# infnoise_usbpins.net
KiCad netlist of a schematic drawn in EAGLE
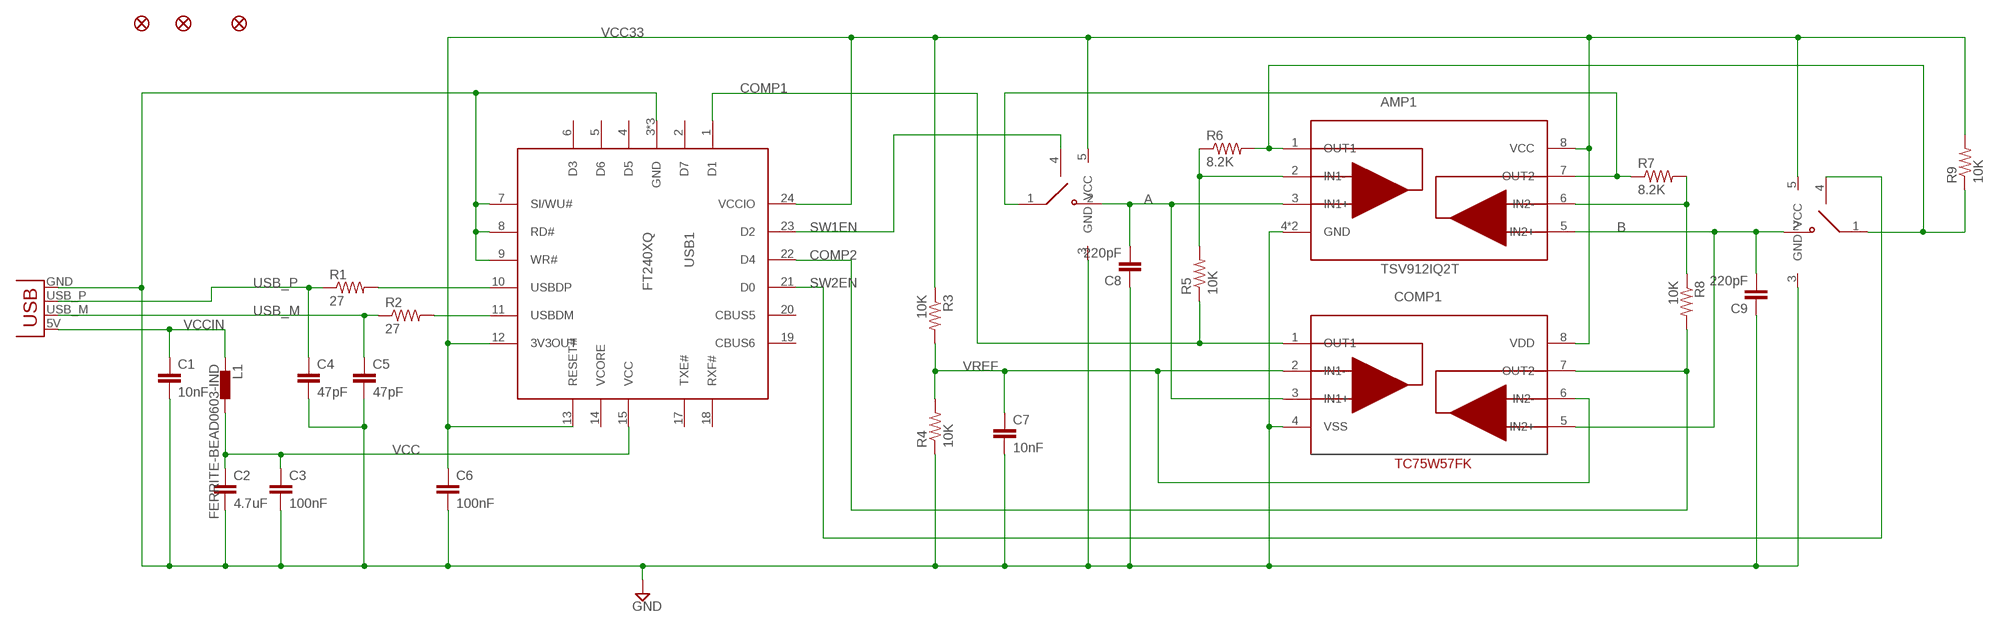
[diagram p0: schematic, sheet 1]

(export (version "E")
  (design (tool "Eeschema 10.0.6"))
  (components
    (comp (ref "AMP1")
      (value "TSV912IQ2T")
      (footprint "eagle-import:DFN8-2X3")
      (libsource (lib "eagle-import") (part "TSV912IQ2T"))
    )
    (comp (ref "C1")
      (value "10nF")
      (footprint "eagle-import:0603-CAP")
      (libsource (lib "eagle-import") (part "CAP0603-CAP"))
    )
    (comp (ref "C2")
      (value "4.7uF")
      (footprint "eagle-import:0603-CAP")
      (libsource (lib "eagle-import") (part "CAP0603-CAP"))
    )
    (comp (ref "C3")
      (value "100nF")
      (footprint "eagle-import:0603-CAP")
      (libsource (lib "eagle-import") (part "CAP0603-CAP"))
    )
    (comp (ref "C4")
      (value "47pF")
      (footprint "eagle-import:0603-CAP")
      (libsource (lib "eagle-import") (part "CAP0603-CAP"))
    )
    (comp (ref "C5")
      (value "47pF")
      (footprint "eagle-import:0603-CAP")
      (libsource (lib "eagle-import") (part "CAP0603-CAP"))
    )
    (comp (ref "C6")
      (value "100nF")
      (footprint "eagle-import:0603-CAP")
      (libsource (lib "eagle-import") (part "CAP0603-CAP"))
    )
    (comp (ref "C7")
      (value "10nF")
      (footprint "eagle-import:0603-CAP")
      (libsource (lib "eagle-import") (part "CAP0603-CAP"))
    )
    (comp (ref "C8")
      (value "220pF")
      (footprint "eagle-import:0603-CAP")
      (libsource (lib "eagle-import") (part "CAP0603-CAP"))
    )
    (comp (ref "C9")
      (value "220pF")
      (footprint "eagle-import:0603-CAP")
      (libsource (lib "eagle-import") (part "CAP0603-CAP"))
    )
    (comp (ref "COMP1")
      (value "TC75W57FK")
      (footprint "eagle-import:SSOP8-P-0.50A")
      (libsource (lib "eagle-import") (part "TC75W57FK"))
    )
    (comp (ref "FID1")
      (value "FIDUCIALUFIDUCIAL")
      (footprint "eagle-import:MICRO-FIDUCIAL")
      (libsource (lib "eagle-import") (part "FIDUCIALUFIDUCIAL"))
    )
    (comp (ref "FID2")
      (value "FIDUCIALUFIDUCIAL")
      (footprint "eagle-import:MICRO-FIDUCIAL")
      (libsource (lib "eagle-import") (part "FIDUCIALUFIDUCIAL"))
    )
    (comp (ref "FID3")
      (value "FIDUCIALUFIDUCIAL")
      (footprint "eagle-import:MICRO-FIDUCIAL")
      (libsource (lib "eagle-import") (part "FIDUCIALUFIDUCIAL"))
    )
    (comp (ref "L1")
      (value "FERRITE-BEAD0603-IND")
      (footprint "eagle-import:0603-IND")
      (libsource (lib "eagle-import") (part "FERRITE-BEAD0603-IND"))
    )
    (comp (ref "R1")
      (value "27")
      (footprint "eagle-import:0603-RES")
      (libsource (lib "eagle-import") (part "RESISTOR0603-RES"))
    )
    (comp (ref "R2")
      (value "27")
      (footprint "eagle-import:0603-RES")
      (libsource (lib "eagle-import") (part "RESISTOR0603-RES"))
    )
    (comp (ref "R3")
      (value "10K")
      (footprint "eagle-import:0603-RES")
      (libsource (lib "eagle-import") (part "RESISTOR0603-RES"))
    )
    (comp (ref "R4")
      (value "10K")
      (footprint "eagle-import:0603-RES")
      (libsource (lib "eagle-import") (part "RESISTOR0603-RES"))
    )
    (comp (ref "R5")
      (value "10K")
      (footprint "eagle-import:0603-RES")
      (libsource (lib "eagle-import") (part "RESISTOR0603-RES"))
    )
    (comp (ref "R6")
      (value "8.2K")
      (footprint "eagle-import:0603-RES")
      (libsource (lib "eagle-import") (part "RESISTOR0603-RES"))
    )
    (comp (ref "R7")
      (value "8.2K")
      (footprint "eagle-import:0603-RES")
      (libsource (lib "eagle-import") (part "RESISTOR0603-RES"))
    )
    (comp (ref "R8")
      (value "10K")
      (footprint "eagle-import:0603-RES")
      (libsource (lib "eagle-import") (part "RESISTOR0603-RES"))
    )
    (comp (ref "R9")
      (value "10K")
      (footprint "eagle-import:0603-RES")
      (libsource (lib "eagle-import") (part "RESISTOR0603-RES"))
    )
    (comp (ref "SW1")
      (value "MC74VHC1G66DFT1G")
      (footprint "eagle-import:SC70-5L")
      (libsource (lib "eagle-import") (part "MC74VHC1G66DFT1G"))
    )
    (comp (ref "SW2")
      (value "MC74VHC1G66DFT1G")
      (footprint "eagle-import:SC70-5L")
      (libsource (lib "eagle-import") (part "MC74VHC1G66DFT1G"))
    )
    (comp (ref "USB1")
      (value "FT240XQ")
      (footprint "eagle-import:QFN24-4X4")
      (libsource (lib "eagle-import") (part "FT240XQ"))
    )
    (comp (ref "X1")
      (value "USBRAWPINS")
      (footprint "eagle-import:USB-A-RAWPINS")
      (libsource (lib "eagle-import") (part "USBRAWPINS"))
    )
  )
  (nets
    (net (code "1") (name "/A") (class "Default")
      (node (ref "AMP1") (pin "3") (pinfunction "IN1+_3") (pintype "bidirectional"))
      (node (ref "C8") (pin "2") (pinfunction "2_2") (pintype "passive"))
      (node (ref "COMP1") (pin "3") (pinfunction "IN1+_3") (pintype "bidirectional"))
      (node (ref "SW1") (pin "2") (pinfunction "NO_2") (pintype "bidirectional"))
    )
    (net (code "2") (name "/B") (class "Default")
      (node (ref "AMP1") (pin "5") (pinfunction "IN2+_5") (pintype "bidirectional"))
      (node (ref "C9") (pin "2") (pinfunction "2_2") (pintype "passive"))
      (node (ref "COMP1") (pin "5") (pinfunction "IN2+_5") (pintype "bidirectional"))
      (node (ref "SW2") (pin "2") (pinfunction "NO_2") (pintype "bidirectional"))
    )
    (net (code "3") (name "/COMP1") (class "Default")
      (node (ref "COMP1") (pin "1") (pinfunction "OUT1_1") (pintype "bidirectional"))
      (node (ref "R5") (pin "1") (pinfunction "1_1") (pintype "passive"))
      (node (ref "USB1") (pin "1") (pinfunction "D1_1") (pintype "bidirectional"))
    )
    (net (code "4") (name "/COMP2") (class "Default")
      (node (ref "COMP1") (pin "7") (pinfunction "OUT2_7") (pintype "bidirectional"))
      (node (ref "R8") (pin "2") (pinfunction "2_2") (pintype "passive"))
      (node (ref "USB1") (pin "22") (pinfunction "D4_22") (pintype "bidirectional"))
    )
    (net (code "5") (name "/SW1EN") (class "Default")
      (node (ref "SW1") (pin "4") (pinfunction "IN_4") (pintype "bidirectional"))
      (node (ref "USB1") (pin "23") (pinfunction "D2_23") (pintype "bidirectional"))
    )
    (net (code "6") (name "/SW2EN") (class "Default")
      (node (ref "SW2") (pin "4") (pinfunction "IN_4") (pintype "bidirectional"))
      (node (ref "USB1") (pin "21") (pinfunction "D0_21") (pintype "bidirectional"))
    )
    (net (code "7") (name "/USB_M") (class "Default")
      (node (ref "C5") (pin "1") (pinfunction "1_1") (pintype "passive"))
      (node (ref "R2") (pin "1") (pinfunction "1_1") (pintype "passive"))
      (node (ref "X1") (pin "USB_M") (pinfunction "D-_USB_M") (pintype "bidirectional"))
    )
    (net (code "8") (name "/USB_P") (class "Default")
      (node (ref "C4") (pin "1") (pinfunction "1_1") (pintype "passive"))
      (node (ref "R1") (pin "1") (pinfunction "1_1") (pintype "passive"))
      (node (ref "X1") (pin "USB_P") (pinfunction "D+_USB_P") (pintype "bidirectional"))
    )
    (net (code "9") (name "/VCC") (class "Default")
      (node (ref "C2") (pin "1") (pinfunction "1_1") (pintype "passive"))
      (node (ref "C3") (pin "1") (pinfunction "1_1") (pintype "passive"))
      (node (ref "L1") (pin "2") (pinfunction "2_2") (pintype "passive"))
      (node (ref "USB1") (pin "15") (pinfunction "VCC_15") (pintype "bidirectional"))
    )
    (net (code "10") (name "/VCC33") (class "Default")
      (node (ref "AMP1") (pin "8") (pinfunction "VCC_8") (pintype "bidirectional"))
      (node (ref "C6") (pin "1") (pinfunction "1_1") (pintype "passive"))
      (node (ref "COMP1") (pin "8") (pinfunction "VDD_8") (pintype "bidirectional"))
      (node (ref "R3") (pin "1") (pinfunction "1_1") (pintype "passive"))
      (node (ref "R9") (pin "2") (pinfunction "2_2") (pintype "passive"))
      (node (ref "SW1") (pin "5") (pinfunction "VCC_5") (pintype "bidirectional"))
      (node (ref "SW2") (pin "5") (pinfunction "VCC_5") (pintype "bidirectional"))
      (node (ref "USB1") (pin "12") (pinfunction "3V3OUT_12") (pintype "bidirectional"))
      (node (ref "USB1") (pin "13") (pinfunction "RESET#_13") (pintype "bidirectional"))
      (node (ref "USB1") (pin "24") (pinfunction "VCCIO_24") (pintype "bidirectional"))
    )
    (net (code "11") (name "/VCCIN") (class "Default")
      (node (ref "C1") (pin "1") (pinfunction "1_1") (pintype "passive"))
      (node (ref "L1") (pin "1") (pinfunction "1_1") (pintype "passive"))
      (node (ref "X1") (pin "5V") (pinfunction "VCC_5V") (pintype "bidirectional"))
    )
    (net (code "12") (name "/VREF") (class "Default")
      (node (ref "C7") (pin "1") (pinfunction "1_1") (pintype "passive"))
      (node (ref "COMP1") (pin "2") (pinfunction "IN1-_2") (pintype "bidirectional"))
      (node (ref "COMP1") (pin "6") (pinfunction "IN2-_6") (pintype "bidirectional"))
      (node (ref "R3") (pin "2") (pinfunction "2_2") (pintype "passive"))
      (node (ref "R4") (pin "2") (pinfunction "2_2") (pintype "passive"))
    )
    (net (code "13") (name "GND") (class "Default")
      (node (ref "AMP1") (pin "4") (pinfunction "GND_4") (pintype "bidirectional"))
      (node (ref "AMP1") (pin "EXP") (pinfunction "GND_EXP") (pintype "bidirectional"))
      (node (ref "C1") (pin "2") (pinfunction "2_2") (pintype "passive"))
      (node (ref "C2") (pin "2") (pinfunction "2_2") (pintype "passive"))
      (node (ref "C3") (pin "2") (pinfunction "2_2") (pintype "passive"))
      (node (ref "C4") (pin "2") (pinfunction "2_2") (pintype "passive"))
      (node (ref "C5") (pin "2") (pinfunction "2_2") (pintype "passive"))
      (node (ref "C6") (pin "2") (pinfunction "2_2") (pintype "passive"))
      (node (ref "C7") (pin "2") (pinfunction "2_2") (pintype "passive"))
      (node (ref "C8") (pin "1") (pinfunction "1_1") (pintype "passive"))
      (node (ref "C9") (pin "1") (pinfunction "1_1") (pintype "passive"))
      (node (ref "COMP1") (pin "4") (pinfunction "VSS_4") (pintype "bidirectional"))
      (node (ref "R4") (pin "1") (pinfunction "1_1") (pintype "passive"))
      (node (ref "SW1") (pin "3") (pinfunction "GND_3") (pintype "bidirectional"))
      (node (ref "SW2") (pin "3") (pinfunction "GND_3") (pintype "bidirectional"))
      (node (ref "USB1") (pin "16") (pinfunction "GND_16") (pintype "bidirectional"))
      (node (ref "USB1") (pin "3") (pinfunction "GND_3") (pintype "bidirectional"))
      (node (ref "USB1") (pin "7") (pinfunction "SI/WU#_7") (pintype "bidirectional"))
      (node (ref "USB1") (pin "8") (pinfunction "RD#_8") (pintype "bidirectional"))
      (node (ref "USB1") (pin "9") (pinfunction "WR#_9") (pintype "bidirectional"))
      (node (ref "USB1") (pin "EXP") (pinfunction "GND_EXP") (pintype "bidirectional"))
      (node (ref "X1") (pin "GND") (pinfunction "GND_GND") (pintype "bidirectional"))
    )
    (net (code "14") (name "Net-(AMP1-IN1-)") (class "Default")
      (node (ref "AMP1") (pin "2") (pinfunction "IN1-_2") (pintype "bidirectional"))
      (node (ref "R5") (pin "2") (pinfunction "2_2") (pintype "passive"))
      (node (ref "R6") (pin "1") (pinfunction "1_1") (pintype "passive"))
    )
    (net (code "15") (name "Net-(AMP1-IN2-)") (class "Default")
      (node (ref "AMP1") (pin "6") (pinfunction "IN2-_6") (pintype "bidirectional"))
      (node (ref "R7") (pin "2") (pinfunction "2_2") (pintype "passive"))
      (node (ref "R8") (pin "1") (pinfunction "1_1") (pintype "passive"))
    )
    (net (code "16") (name "Net-(AMP1-OUT1)") (class "Default")
      (node (ref "AMP1") (pin "1") (pinfunction "OUT1_1") (pintype "bidirectional"))
      (node (ref "R6") (pin "2") (pinfunction "2_2") (pintype "passive"))
      (node (ref "R9") (pin "1") (pinfunction "1_1") (pintype "passive"))
      (node (ref "SW2") (pin "1") (pinfunction "COM_1") (pintype "bidirectional"))
    )
    (net (code "17") (name "Net-(AMP1-OUT2)") (class "Default")
      (node (ref "AMP1") (pin "7") (pinfunction "OUT2_7") (pintype "bidirectional"))
      (node (ref "R7") (pin "1") (pinfunction "1_1") (pintype "passive"))
      (node (ref "SW1") (pin "1") (pinfunction "COM_1") (pintype "bidirectional"))
    )
    (net (code "18") (name "Net-(USB1-USBDM)") (class "Default")
      (node (ref "R2") (pin "2") (pinfunction "2_2") (pintype "passive"))
      (node (ref "USB1") (pin "11") (pinfunction "USBDM_11") (pintype "bidirectional"))
    )
    (net (code "19") (name "Net-(USB1-USBDP)") (class "Default")
      (node (ref "R1") (pin "2") (pinfunction "2_2") (pintype "passive"))
      (node (ref "USB1") (pin "10") (pinfunction "USBDP_10") (pintype "bidirectional"))
    )
    (net (code "20") (name "unconnected-(USB1-CBUS5-Pad20)") (class "Default")
      (node (ref "USB1") (pin "20") (pinfunction "CBUS5_20") (pintype "bidirectional"))
    )
    (net (code "21") (name "unconnected-(USB1-CBUS6-Pad19)") (class "Default")
      (node (ref "USB1") (pin "19") (pinfunction "CBUS6_19") (pintype "bidirectional"))
    )
    (net (code "22") (name "unconnected-(USB1-D3-Pad6)") (class "Default")
      (node (ref "USB1") (pin "6") (pinfunction "D3_6") (pintype "bidirectional"))
    )
    (net (code "23") (name "unconnected-(USB1-D5-Pad4)") (class "Default")
      (node (ref "USB1") (pin "4") (pinfunction "D5_4") (pintype "bidirectional"))
    )
    (net (code "24") (name "unconnected-(USB1-D6-Pad5)") (class "Default")
      (node (ref "USB1") (pin "5") (pinfunction "D6_5") (pintype "bidirectional"))
    )
    (net (code "25") (name "unconnected-(USB1-D7-Pad2)") (class "Default")
      (node (ref "USB1") (pin "2") (pinfunction "D7_2") (pintype "bidirectional"))
    )
    (net (code "26") (name "unconnected-(USB1-RXF#-Pad18)") (class "Default")
      (node (ref "USB1") (pin "18") (pinfunction "RXF#_18") (pintype "bidirectional"))
    )
    (net (code "27") (name "unconnected-(USB1-TXE#-Pad17)") (class "Default")
      (node (ref "USB1") (pin "17") (pinfunction "TXE#_17") (pintype "bidirectional"))
    )
    (net (code "28") (name "unconnected-(USB1-VCORE-Pad14)") (class "Default")
      (node (ref "USB1") (pin "14") (pinfunction "VCORE_14") (pintype "bidirectional"))
    )
  )
)
